# SCH_LEDS.net
KiCad netlist of a schematic drawn in Altium Designer
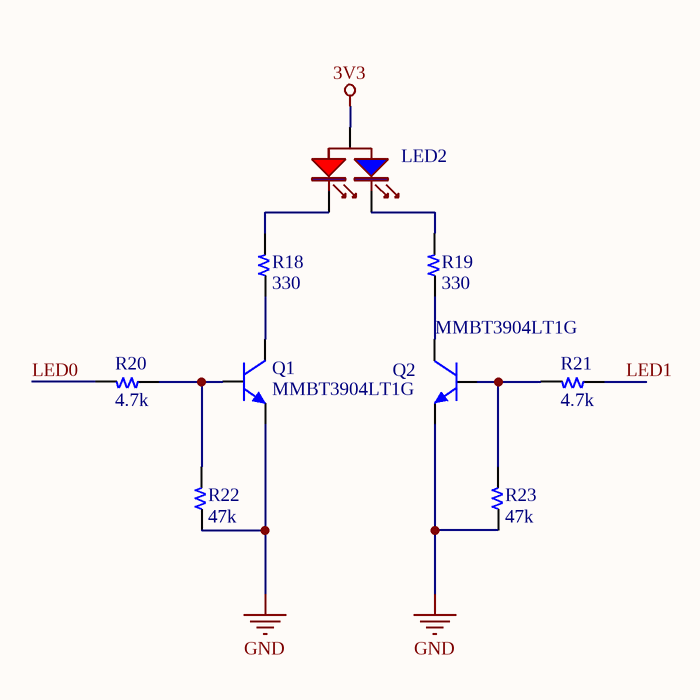
[diagram p0: SCH_LEDS.SchDoc]

(export (version "E")
  (design (tool "Eeschema 10.0.6"))
  (components
    (comp (ref "LED2")
      (value "RB LED")
      (footprint "LED-BICOLOR-3MM")
      (description "Bicolor RB 3mm LED")
      (libsource (lib "led") (part "LED 2-color-A"))
    )
    (comp (ref "Q1")
      (value "MMBT3904LT1G")
      (footprint "SOT-23")
      (description "NPN Bipolar Transistor")
      (libsource (lib "chipfc_libs") (part "Transistor NPN"))
    )
    (comp (ref "Q2")
      (value "MMBT3904LT1G")
      (footprint "SOT-23")
      (description "NPN Bipolar Transistor")
      (libsource (lib "chipfc_libs") (part "Transistor NPN"))
    )
    (comp (ref "R18")
      (value "330")
      (footprint "R 0603")
      (description "Resistor")
      (libsource (lib "chipfc_libs") (part "Resistor"))
    )
    (comp (ref "R19")
      (value "330")
      (footprint "R 0603")
      (description "Resistor")
      (libsource (lib "chipfc_libs") (part "Resistor"))
    )
    (comp (ref "R20")
      (value "4.7k")
      (footprint "R 0603")
      (description "Resistor")
      (libsource (lib "chipfc_libs") (part "Resistor"))
    )
    (comp (ref "R21")
      (value "4.7k")
      (footprint "R 0603")
      (description "Resistor")
      (libsource (lib "chipfc_libs") (part "Resistor"))
    )
    (comp (ref "R22")
      (value "47k")
      (footprint "R 0603")
      (description "Resistor")
      (libsource (lib "chipfc_libs") (part "Resistor"))
    )
    (comp (ref "R23")
      (value "47k")
      (footprint "R 0603")
      (description "Resistor")
      (libsource (lib "chipfc_libs") (part "Resistor"))
    )
  )
  (nets
    (net (code "1") (name "/LED0") (class "Default")
      (node (ref "R20") (pin "2") (pinfunction "2_2") (pintype "passive"))
    )
    (net (code "2") (name "/LED1") (class "Default")
      (node (ref "R21") (pin "1") (pinfunction "1_1") (pintype "passive"))
    )
    (net (code "3") (name "3V3") (class "Default")
      (node (ref "LED2") (pin "2") (pinfunction "A_2") (pintype "passive"))
    )
    (net (code "4") (name "GND") (class "Default")
      (node (ref "Q1") (pin "2") (pinfunction "E_2") (pintype "passive"))
      (node (ref "Q2") (pin "2") (pinfunction "E_2") (pintype "passive"))
      (node (ref "R22") (pin "1") (pinfunction "1_1") (pintype "passive"))
      (node (ref "R23") (pin "1") (pinfunction "1_1") (pintype "passive"))
    )
    (net (code "5") (name "Net-(LED2-K1)") (class "Default")
      (node (ref "LED2") (pin "1") (pinfunction "K1_1") (pintype "passive"))
      (node (ref "R18") (pin "2") (pinfunction "2_2") (pintype "passive"))
    )
    (net (code "6") (name "Net-(LED2-K2)") (class "Default")
      (node (ref "LED2") (pin "3") (pinfunction "K2_3") (pintype "passive"))
      (node (ref "R19") (pin "2") (pinfunction "2_2") (pintype "passive"))
    )
    (net (code "7") (name "Net-(Q1-B)") (class "Default")
      (node (ref "Q1") (pin "1") (pinfunction "B_1") (pintype "passive"))
      (node (ref "R20") (pin "1") (pinfunction "1_1") (pintype "passive"))
      (node (ref "R22") (pin "2") (pinfunction "2_2") (pintype "passive"))
    )
    (net (code "8") (name "Net-(Q1-C)") (class "Default")
      (node (ref "Q1") (pin "3") (pinfunction "C_3") (pintype "passive"))
      (node (ref "R18") (pin "1") (pinfunction "1_1") (pintype "passive"))
    )
    (net (code "9") (name "Net-(Q2-B)") (class "Default")
      (node (ref "Q2") (pin "1") (pinfunction "B_1") (pintype "passive"))
      (node (ref "R21") (pin "2") (pinfunction "2_2") (pintype "passive"))
      (node (ref "R23") (pin "2") (pinfunction "2_2") (pintype "passive"))
    )
    (net (code "10") (name "Net-(Q2-C)") (class "Default")
      (node (ref "Q2") (pin "3") (pinfunction "C_3") (pintype "passive"))
      (node (ref "R19") (pin "1") (pinfunction "1_1") (pintype "passive"))
    )
  )
)
